# Top-PCB.net
KiCad netlist of a schematic drawn in Altium Designer
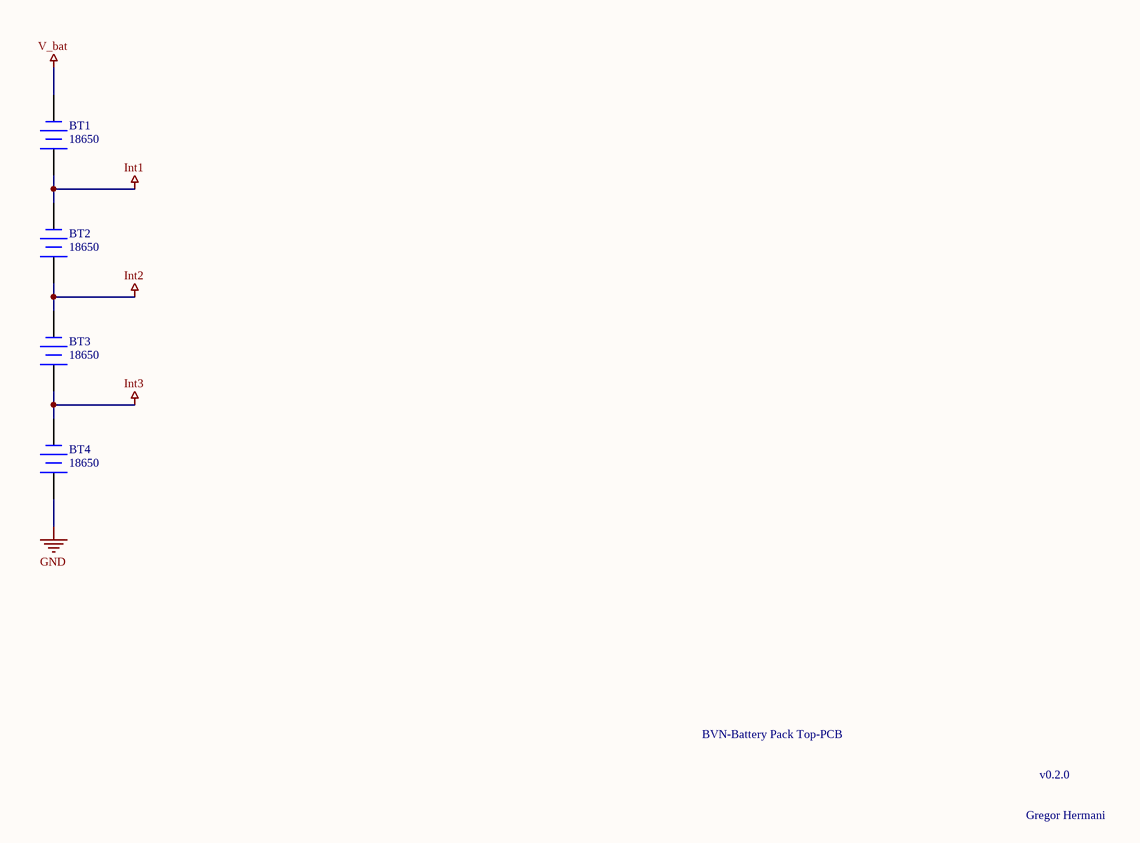
[diagram p0: Top-PCB.SchDoc]

(export (version "E")
  (design (tool "Eeschema 10.0.6"))
  (components
    (comp (ref "BT1")
      (value "18650")
      (footprint "BAT-2")
      (description "Multicell Battery")
      (fields (field (name "PUBLISHER") "Altium Limited"))
      (libsource (lib "Miscellaneous Devices") (part "Battery"))
    )
    (comp (ref "BT2")
      (value "18650")
      (footprint "BAT-2")
      (description "Multicell Battery")
      (fields (field (name "PUBLISHER") "Altium Limited"))
      (libsource (lib "Miscellaneous Devices") (part "Battery"))
    )
    (comp (ref "BT3")
      (value "18650")
      (footprint "BAT-2")
      (description "Multicell Battery")
      (fields (field (name "PUBLISHER") "Altium Limited"))
      (libsource (lib "Miscellaneous Devices") (part "Battery"))
    )
    (comp (ref "BT4")
      (value "18650")
      (footprint "BAT-2")
      (description "Multicell Battery")
      (fields (field (name "PUBLISHER") "Altium Limited"))
      (libsource (lib "Miscellaneous Devices") (part "Battery"))
    )
  )
  (nets
    (net (code "1") (name "GND") (class "Default")
      (node (ref "BT4") (pin "1") (pinfunction "+_1") (pintype "passive"))
    )
    (net (code "2") (name "Int1") (class "Default")
      (node (ref "BT1") (pin "1") (pinfunction "+_1") (pintype "passive"))
      (node (ref "BT2") (pin "2") (pinfunction "-_2") (pintype "passive"))
    )
    (net (code "3") (name "Int2") (class "Default")
      (node (ref "BT2") (pin "1") (pinfunction "+_1") (pintype "passive"))
      (node (ref "BT3") (pin "2") (pinfunction "-_2") (pintype "passive"))
    )
    (net (code "4") (name "Int3") (class "Default")
      (node (ref "BT3") (pin "1") (pinfunction "+_1") (pintype "passive"))
      (node (ref "BT4") (pin "2") (pinfunction "-_2") (pintype "passive"))
    )
    (net (code "5") (name "V_bat") (class "Default")
      (node (ref "BT1") (pin "2") (pinfunction "-_2") (pintype "passive"))
    )
  )
)
